# 12_Key.net
KiCad netlist of a schematic drawn in Altium Designer
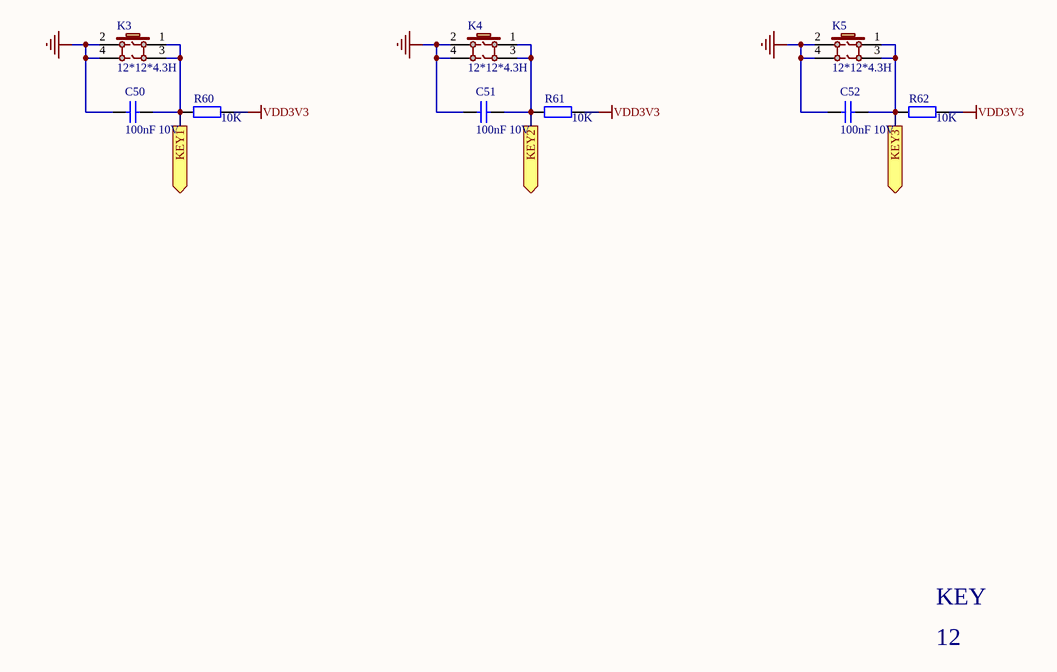
[diagram p0: 12_Key.SchDoc]

(export (version "E")
  (design (tool "Eeschema 10.0.6"))
  (components
    (comp (ref "C50")
      (value "100nF 10V")
      (footprint "SMD-0603C")
      (description "贴片电容 20%")
      (libsource (lib "XiaoyI") (part "CAP4"))
    )
    (comp (ref "C51")
      (value "100nF 10V")
      (footprint "SMD-0603C")
      (description "贴片电容 20%")
      (libsource (lib "XiaoyI") (part "CAP4"))
    )
    (comp (ref "C52")
      (value "100nF 10V")
      (footprint "SMD-0603C")
      (description "贴片电容 20%")
      (libsource (lib "XiaoyI") (part "CAP4"))
    )
    (comp (ref "K3")
      (value "12*12*4.3H")
      (footprint "KEY-SMD12*12*4.3")
      (libsource (lib "Sch_library") (part "KEY2"))
    )
    (comp (ref "K4")
      (value "12*12*4.3H")
      (footprint "KEY-SMD12*12*4.3")
      (libsource (lib "Sch_library") (part "KEY2"))
    )
    (comp (ref "K5")
      (value "12*12*4.3H")
      (footprint "KEY-SMD12*12*4.3")
      (libsource (lib "Sch_library") (part "KEY2"))
    )
    (comp (ref "R60")
      (value "10K")
      (footprint "SMD-0603")
      (description "贴片电阻 5%")
      (libsource (lib "ABB") (part "RES0"))
    )
    (comp (ref "R61")
      (value "10K")
      (footprint "SMD-0603")
      (description "贴片电阻 5%")
      (libsource (lib "ABB") (part "RES0"))
    )
    (comp (ref "R62")
      (value "10K")
      (footprint "SMD-0603")
      (description "贴片电阻 5%")
      (libsource (lib "ABB") (part "RES0"))
    )
  )
  (nets
    (net (code "1") (name "/KEY1") (class "Default")
      (node (ref "C50") (pin "1") (pinfunction "1_1") (pintype "passive"))
      (node (ref "K3") (pin "1") (pinfunction "1_1") (pintype "passive"))
      (node (ref "K3") (pin "3") (pinfunction "3_3") (pintype "passive"))
      (node (ref "R60") (pin "1") (pinfunction "1_1") (pintype "passive"))
    )
    (net (code "2") (name "/KEY2") (class "Default")
      (node (ref "C51") (pin "1") (pinfunction "1_1") (pintype "passive"))
      (node (ref "K4") (pin "1") (pinfunction "1_1") (pintype "passive"))
      (node (ref "K4") (pin "3") (pinfunction "3_3") (pintype "passive"))
      (node (ref "R61") (pin "1") (pinfunction "1_1") (pintype "passive"))
    )
    (net (code "3") (name "/KEY3") (class "Default")
      (node (ref "C52") (pin "1") (pinfunction "1_1") (pintype "passive"))
      (node (ref "K5") (pin "1") (pinfunction "1_1") (pintype "passive"))
      (node (ref "K5") (pin "3") (pinfunction "3_3") (pintype "passive"))
      (node (ref "R62") (pin "1") (pinfunction "1_1") (pintype "passive"))
    )
    (net (code "4") (name "GND") (class "Default")
      (node (ref "C50") (pin "2") (pinfunction "2_2") (pintype "passive"))
      (node (ref "C51") (pin "2") (pinfunction "2_2") (pintype "passive"))
      (node (ref "C52") (pin "2") (pinfunction "2_2") (pintype "passive"))
      (node (ref "K3") (pin "2") (pinfunction "2_2") (pintype "passive"))
      (node (ref "K3") (pin "4") (pinfunction "4_4") (pintype "passive"))
      (node (ref "K4") (pin "2") (pinfunction "2_2") (pintype "passive"))
      (node (ref "K4") (pin "4") (pinfunction "4_4") (pintype "passive"))
      (node (ref "K5") (pin "2") (pinfunction "2_2") (pintype "passive"))
      (node (ref "K5") (pin "4") (pinfunction "4_4") (pintype "passive"))
    )
    (net (code "5") (name "VDD3V3") (class "Default")
      (node (ref "R60") (pin "2") (pinfunction "2_2") (pintype "passive"))
      (node (ref "R61") (pin "2") (pinfunction "2_2") (pintype "passive"))
      (node (ref "R62") (pin "2") (pinfunction "2_2") (pintype "passive"))
    )
  )
)
